# Youtube_Motherboard.net
KiCad netlist of a schematic drawn in Altium Designer
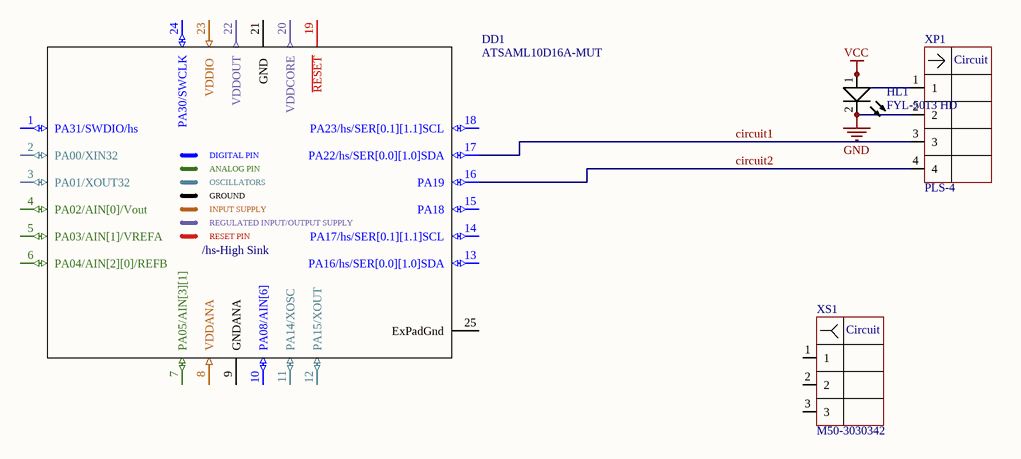
[diagram p0: Youtube_Motherboard.SchDoc]

(export (version "E")
  (design (tool "Eeschema 10.0.6"))
  (components
    (comp (ref "DD1")
      (value "ATSAML10D16A-MUT")
      (footprint "VQFN-24")
      (description "IC MCU 32BIT 64KB FLASH 24VQFN,ARM® Cortex®-M23")
      (fields (field (name "DIGI-KEY PART NUMBER") "ATSAML10D16A-MUTCT-ND"))
      (libsource (lib "SssAccesDatbase") (part "ATSAML10D16A-MUT"))
    )
    (comp (ref "HL1")
      (value "FYL-5013 HD")
      (footprint "LED_3MM_RED")
      (libsource (lib "SssAccesDatbase") (part "LED_12"))
    )
    (comp (ref "XP1")
      (value "PLS-4")
      (footprint "PLS-4-3D")
      (fields
        (field (name "PART NUMBER") "G800W304018EU")
        (field (name "MOUSER PART NUMBER") "523-G800W304018EU")
      )
      (libsource (lib "SssAccesDatbase") (part "XP-4"))
    )
    (comp (ref "XS1")
      (value "M50-3030342")
      (footprint "PBLS-1.27-3")
      (description "Headers & Wire Housings 3 WAY SIL VERT PC TAIL SKT")
      (fields (field (name "MOUSER PART NUMBER") "855-M50-3030342"))
      (libsource (lib "SssAccesDatbase") (part "XS-3"))
    )
  )
  (nets
    (net (code "1") (name "/circuit1") (class "Default")
      (node (ref "DD1") (pin "17") (pinfunction "PA22/hs/SER[0.0][1.0]SDA_17") (pintype "bidirectional"))
      (node (ref "XP1") (pin "3") (pinfunction "3_3") (pintype "passive"))
    )
    (net (code "2") (name "/circuit2") (class "Default")
      (node (ref "DD1") (pin "16") (pinfunction "PA19_16") (pintype "bidirectional"))
      (node (ref "XP1") (pin "4") (pinfunction "4_4") (pintype "passive"))
    )
    (net (code "3") (name "GND") (class "Default")
      (node (ref "HL1") (pin "2") (pinfunction "K_2") (pintype "passive"))
      (node (ref "XP1") (pin "2") (pinfunction "2_2") (pintype "passive"))
    )
    (net (code "4") (name "VCC") (class "Default")
      (node (ref "HL1") (pin "1") (pinfunction "A_1") (pintype "passive"))
      (node (ref "XP1") (pin "1") (pinfunction "1_1") (pintype "passive"))
    )
    (net (code "5") (name "unconnected-(DD1-ExPadGnd-Pad25)") (class "Default")
      (node (ref "DD1") (pin "25") (pinfunction "ExPadGnd_25") (pintype "passive"))
    )
    (net (code "6") (name "unconnected-(DD1-GND-Pad21)") (class "Default")
      (node (ref "DD1") (pin "21") (pinfunction "GND_21") (pintype "passive"))
    )
    (net (code "7") (name "unconnected-(DD1-GNDANA-Pad9)") (class "Default")
      (node (ref "DD1") (pin "9") (pinfunction "GNDANA_9") (pintype "passive"))
    )
    (net (code "8") (name "unconnected-(DD1-PA00{slash}XIN32-Pad2)") (class "Default")
      (node (ref "DD1") (pin "2") (pinfunction "PA00/XIN32_2") (pintype "bidirectional"))
    )
    (net (code "9") (name "unconnected-(DD1-PA01{slash}XOUT32-Pad3)") (class "Default")
      (node (ref "DD1") (pin "3") (pinfunction "PA01/XOUT32_3") (pintype "bidirectional"))
    )
    (net (code "10") (name "unconnected-(DD1-PA02{slash}AIN[0]{slash}Vout-Pad4)") (class "Default")
      (node (ref "DD1") (pin "4") (pinfunction "PA02/AIN[0]/Vout_4") (pintype "bidirectional"))
    )
    (net (code "11") (name "unconnected-(DD1-PA03{slash}AIN[1]{slash}VREFA-Pad5)") (class "Default")
      (node (ref "DD1") (pin "5") (pinfunction "PA03/AIN[1]/VREFA_5") (pintype "bidirectional"))
    )
    (net (code "12") (name "unconnected-(DD1-PA04{slash}AIN[2][0]{slash}REFB-Pad6)") (class "Default")
      (node (ref "DD1") (pin "6") (pinfunction "PA04/AIN[2][0]/REFB_6") (pintype "bidirectional"))
    )
    (net (code "13") (name "unconnected-(DD1-PA05{slash}AIN[3][1]-Pad7)") (class "Default")
      (node (ref "DD1") (pin "7") (pinfunction "PA05/AIN[3][1]_7") (pintype "bidirectional"))
    )
    (net (code "14") (name "unconnected-(DD1-PA08{slash}AIN[6]-Pad10)") (class "Default")
      (node (ref "DD1") (pin "10") (pinfunction "PA08/AIN[6]_10") (pintype "bidirectional"))
    )
    (net (code "15") (name "unconnected-(DD1-PA14{slash}XOSC-Pad11)") (class "Default")
      (node (ref "DD1") (pin "11") (pinfunction "PA14/XOSC_11") (pintype "bidirectional"))
    )
    (net (code "16") (name "unconnected-(DD1-PA15{slash}XOUT-Pad12)") (class "Default")
      (node (ref "DD1") (pin "12") (pinfunction "PA15/XOUT_12") (pintype "bidirectional"))
    )
    (net (code "17") (name "unconnected-(DD1-PA16{slash}hs{slash}SER[0.0][1.0]SDA-Pad13)") (class "Default")
      (node (ref "DD1") (pin "13") (pinfunction "PA16/hs/SER[0.0][1.0]SDA_13") (pintype "bidirectional"))
    )
    (net (code "18") (name "unconnected-(DD1-PA17{slash}hs{slash}SER[0.1][1.1]SCL-Pad14)") (class "Default")
      (node (ref "DD1") (pin "14") (pinfunction "PA17/hs/SER[0.1][1.1]SCL_14") (pintype "bidirectional"))
    )
    (net (code "19") (name "unconnected-(DD1-PA18-Pad15)") (class "Default")
      (node (ref "DD1") (pin "15") (pinfunction "PA18_15") (pintype "bidirectional"))
    )
    (net (code "20") (name "unconnected-(DD1-PA23{slash}hs{slash}SER[0.1][1.1]SCL-Pad18)") (class "Default")
      (node (ref "DD1") (pin "18") (pinfunction "PA23/hs/SER[0.1][1.1]SCL_18") (pintype "bidirectional"))
    )
    (net (code "21") (name "unconnected-(DD1-PA30{slash}SWCLK-Pad24)") (class "Default")
      (node (ref "DD1") (pin "24") (pinfunction "PA30/SWCLK_24") (pintype "bidirectional"))
    )
    (net (code "22") (name "unconnected-(DD1-PA31{slash}SWDIO{slash}hs-Pad1)") (class "Default")
      (node (ref "DD1") (pin "1") (pinfunction "PA31/SWDIO/hs_1") (pintype "bidirectional"))
    )
    (net (code "23") (name "unconnected-(DD1-VDDANA-Pad8)") (class "Default")
      (node (ref "DD1") (pin "8") (pinfunction "VDDANA_8") (pintype "input"))
    )
    (net (code "24") (name "unconnected-(DD1-VDDCORE-Pad20)") (class "Default")
      (node (ref "DD1") (pin "20") (pinfunction "VDDCORE_20") (pintype "output"))
    )
    (net (code "25") (name "unconnected-(DD1-VDDIO-Pad23)") (class "Default")
      (node (ref "DD1") (pin "23") (pinfunction "VDDIO_23") (pintype "input"))
    )
    (net (code "26") (name "unconnected-(DD1-VDDOUT-Pad22)") (class "Default")
      (node (ref "DD1") (pin "22") (pinfunction "VDDOUT_22") (pintype "output"))
    )
    (net (code "27") (name "unconnected-(DD1-~{RESET}-Pad19)") (class "Default")
      (node (ref "DD1") (pin "19") (pinfunction "~{RESET}_19") (pintype "passive"))
    )
    (net (code "28") (name "unconnected-(XS1-Pad1)") (class "Default")
      (node (ref "XS1") (pin "1") (pinfunction "1_1") (pintype "passive"))
    )
    (net (code "29") (name "unconnected-(XS1-Pad2)") (class "Default")
      (node (ref "XS1") (pin "2") (pinfunction "2_2") (pintype "passive"))
    )
    (net (code "30") (name "unconnected-(XS1-Pad3)") (class "Default")
      (node (ref "XS1") (pin "3") (pinfunction "3_3") (pintype "passive"))
    )
  )
)
